# Sheet1.net
KiCad netlist of a schematic drawn in Altium Designer
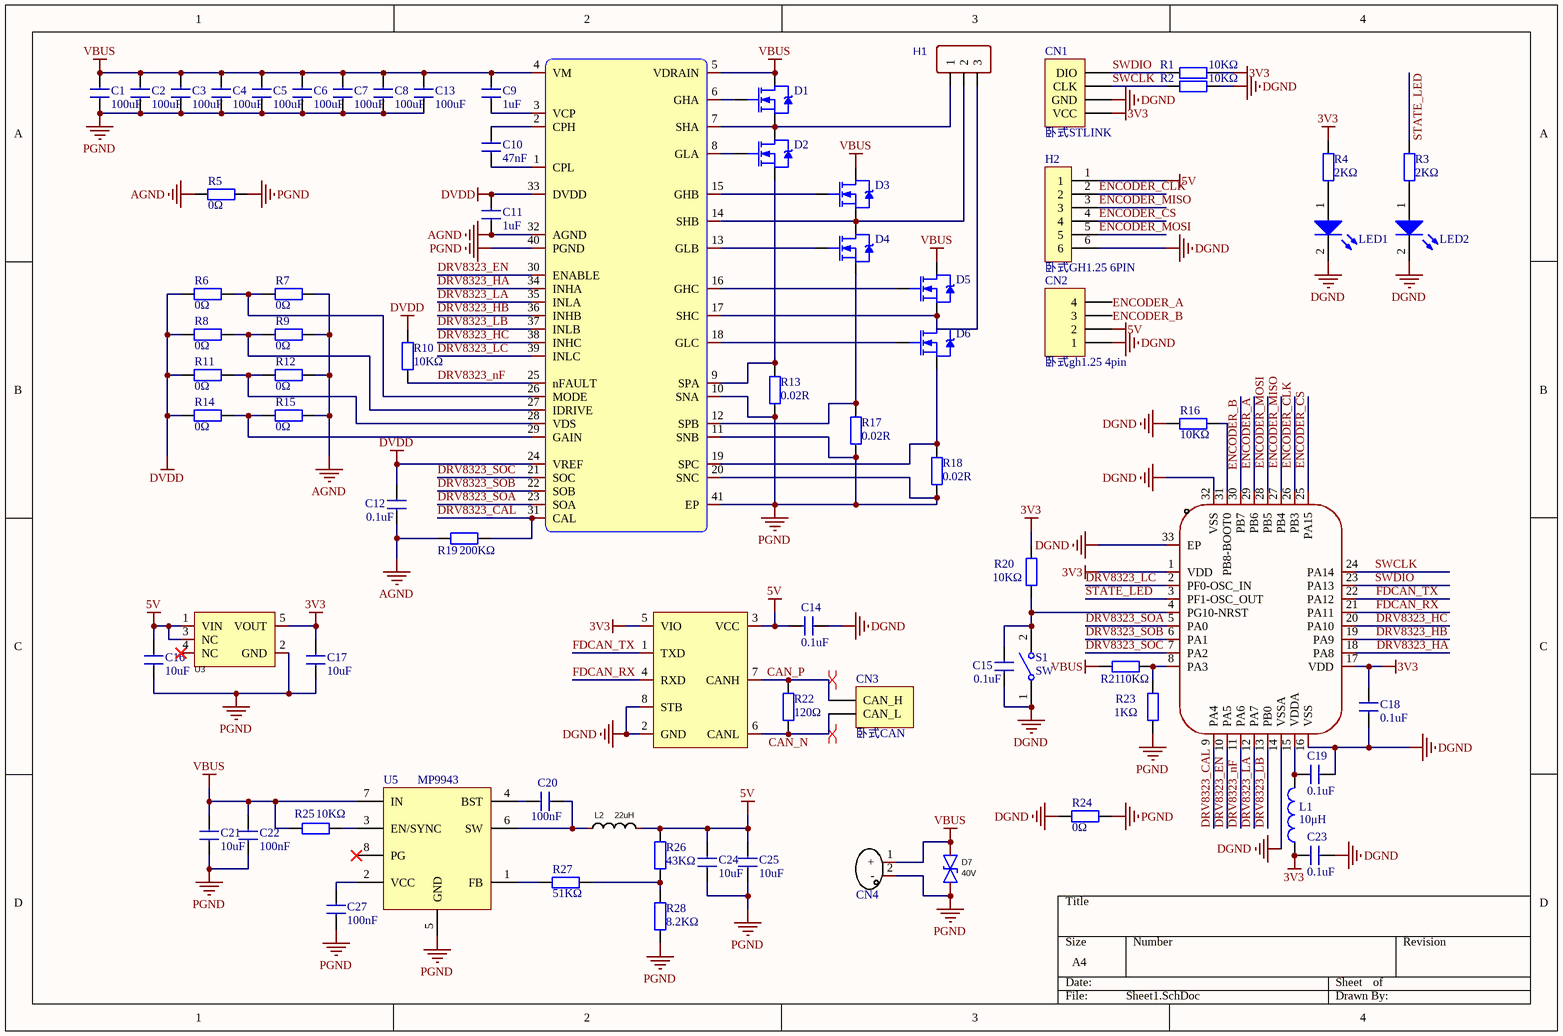
[diagram p0: Sheet1.SchDoc]

(export (version "E")
  (design (tool "Eeschema 10.0.6"))
  (components
    (comp (ref "C1")
      (value "100uF")
      (footprint "1210")
      (description "1210贴片电容")
      (libsource (lib "Integrated_Library1") (part "1210贴片电容"))
    )
    (comp (ref "C2")
      (value "100uF")
      (footprint "1210")
      (description "1210贴片电容")
      (libsource (lib "Integrated_Library1") (part "1210贴片电容"))
    )
    (comp (ref "C3")
      (value "100uF")
      (footprint "1210")
      (description "1210贴片电容")
      (libsource (lib "Integrated_Library1") (part "1210贴片电容"))
    )
    (comp (ref "C4")
      (value "100uF")
      (footprint "1210")
      (description "1210贴片电容")
      (libsource (lib "Integrated_Library1") (part "1210贴片电容"))
    )
    (comp (ref "C5")
      (value "100uF")
      (footprint "1210")
      (description "1210贴片电容")
      (libsource (lib "Integrated_Library1") (part "1210贴片电容"))
    )
    (comp (ref "C6")
      (value "100uF")
      (footprint "1210")
      (description "1210贴片电容")
      (libsource (lib "Integrated_Library1") (part "1210贴片电容"))
    )
    (comp (ref "C7")
      (value "100uF")
      (footprint "1210")
      (description "1210贴片电容")
      (libsource (lib "Integrated_Library1") (part "1210贴片电容"))
    )
    (comp (ref "C8")
      (value "100uF")
      (footprint "1210")
      (description "1210贴片电容")
      (libsource (lib "Integrated_Library1") (part "1210贴片电容"))
    )
    (comp (ref "C9")
      (value "1uF")
      (footprint "c0402")
      (description "贴片电容0402")
      (libsource (lib "Integrated_Library1") (part "0402贴片电容"))
    )
    (comp (ref "C10")
      (value "47nF")
      (footprint "c0402")
      (description "贴片电容0402")
      (libsource (lib "Integrated_Library1") (part "0402贴片电容"))
    )
    (comp (ref "C11")
      (value "1uF")
      (footprint "c0402")
      (description "贴片电容0402")
      (libsource (lib "Integrated_Library1") (part "0402贴片电容"))
    )
    (comp (ref "C12")
      (value "0.1uF")
      (footprint "c0402")
      (description "贴片电容0402")
      (libsource (lib "Integrated_Library1") (part "0402贴片电容"))
    )
    (comp (ref "C13")
      (value "100uF")
      (footprint "1210")
      (description "1210贴片电容")
      (libsource (lib "Integrated_Library1") (part "1210贴片电容"))
    )
    (comp (ref "C14")
      (value "0.1uF")
      (footprint "c0402")
      (description "贴片电容0402")
      (libsource (lib "Integrated_Library1") (part "0402贴片电容"))
    )
    (comp (ref "C15")
      (value "0.1uF")
      (footprint "c0402")
      (description "贴片电容0402")
      (libsource (lib "Integrated_Library1") (part "0402贴片电容"))
    )
    (comp (ref "C16")
      (value "10uF")
      (footprint "c0402")
      (description "贴片电容0402")
      (libsource (lib "Integrated_Library1") (part "0402贴片电容"))
    )
    (comp (ref "C17")
      (value "10uF")
      (footprint "c0402")
      (description "贴片电容0402")
      (libsource (lib "Integrated_Library1") (part "0402贴片电容"))
    )
    (comp (ref "C18")
      (value "0.1uF")
      (footprint "c0402")
      (description "贴片电容0402")
      (libsource (lib "Integrated_Library1") (part "0402贴片电容"))
    )
    (comp (ref "C19")
      (value "0.1uF")
      (footprint "c0402")
      (description "贴片电容0402")
      (libsource (lib "Integrated_Library1") (part "0402贴片电容"))
    )
    (comp (ref "C20")
      (value "100nF")
      (footprint "c0402")
      (description "贴片电容0402")
      (libsource (lib "Integrated_Library1") (part "0402贴片电容"))
    )
    (comp (ref "C21")
      (value "10uF")
      (footprint "1210")
      (description "1210贴片电容")
      (libsource (lib "Integrated_Library1") (part "1210贴片电容"))
    )
    (comp (ref "C22")
      (value "100nF")
      (footprint "c0402")
      (description "贴片电容0402")
      (libsource (lib "Integrated_Library1") (part "0402贴片电容"))
    )
    (comp (ref "C23")
      (value "0.1uF")
      (footprint "c0402")
      (description "贴片电容0402")
      (libsource (lib "Integrated_Library1") (part "0402贴片电容"))
    )
    (comp (ref "C24")
      (value "10uF")
      (footprint "1210")
      (description "1210贴片电容")
      (libsource (lib "Integrated_Library1") (part "1210贴片电容"))
    )
    (comp (ref "C25")
      (value "10uF")
      (footprint "1210")
      (description "1210贴片电容")
      (libsource (lib "Integrated_Library1") (part "1210贴片电容"))
    )
    (comp (ref "C27")
      (value "100nF")
      (footprint "c0402")
      (description "贴片电容0402")
      (libsource (lib "Integrated_Library1") (part "0402贴片电容"))
    )
    (comp (ref "CN1")
      (value "卧式STLINK")
      (footprint "CONN-SMD_4P-P1.25_GH1.25-4P")
      (libsource (lib "Integrated_Library1") (part "卧式STLINK"))
    )
    (comp (ref "CN2")
      (value "卧式gh1.25 4pin")
      (footprint "CONN-SMD_4P-P1.25_GH1.25-4P")
      (libsource (lib "Integrated_Library1") (part "卧式gh1.25 4pin"))
    )
    (comp (ref "CN3")
      (value "卧式CAN")
      (footprint "A1257WR-S-2P")
      (fields (field (name "PUBLISHER") "Altium Limited"))
      (libsource (lib "Integrated_Library1") (part "卧式CAN"))
    )
    (comp (ref "CN4")
      (value "卧贴立式XT30母头")
      (footprint "CONN-TH_XT30U-M _Sleep")
      (libsource (lib "Integrated_Library1") (part "卧贴立式XT30母头"))
    )
    (comp (ref "D1")
      (value "CSD18540")
      (footprint "pg-tdson-8")
      (description "N沟道MOS管")
      (fields (field (name "PUBLISHER") "Altium Limited"))
      (libsource (lib "Integrated_Library1") (part "CSD18540"))
    )
    (comp (ref "D2")
      (value "CSD18540")
      (footprint "pg-tdson-8")
      (description "N沟道MOS管")
      (fields (field (name "PUBLISHER") "Altium Limited"))
      (libsource (lib "Integrated_Library1") (part "CSD18540"))
    )
    (comp (ref "D3")
      (value "CSD18540")
      (footprint "pg-tdson-8")
      (description "N沟道MOS管")
      (fields (field (name "PUBLISHER") "Altium Limited"))
      (libsource (lib "Integrated_Library1") (part "CSD18540"))
    )
    (comp (ref "D4")
      (value "CSD18540")
      (footprint "pg-tdson-8")
      (description "N沟道MOS管")
      (fields (field (name "PUBLISHER") "Altium Limited"))
      (libsource (lib "Integrated_Library1") (part "CSD18540"))
    )
    (comp (ref "D5")
      (value "CSD18540")
      (footprint "pg-tdson-8")
      (description "N沟道MOS管")
      (fields (field (name "PUBLISHER") "Altium Limited"))
      (libsource (lib "Integrated_Library1") (part "CSD18540"))
    )
    (comp (ref "D6")
      (value "CSD18540")
      (footprint "pg-tdson-8")
      (description "N沟道MOS管")
      (fields (field (name "PUBLISHER") "Altium Limited"))
      (libsource (lib "Integrated_Library1") (part "CSD18540"))
    )
    (comp (ref "D7")
      (value "40V")
      (footprint "SMB_L4.6-W3.6-LS5.3-BI")
      (description "28V 双向TVS")
      (fields (field (name "MANUFACTURER") "Littelfuse(美国力特)") (field (name "MANUFACTURER PART") "P6SMB30CA"))
      (libsource (lib "Integrated_Library1") (part "P6SMB30CA"))
    )
    (comp (ref "H1")
      (value "MR30-M")
      (footprint "MR30")
      (fields (field (name "BOM_SUPPLIER PART") "C99873") (field (name "CONTRIBUTOR") "LCEDA_Lib"))
      (libsource (lib "Integrated_Library1") (part "MR30-M"))
    )
    (comp (ref "H2")
      (value "卧式GH1.25 6PIN")
      (footprint "CONN-SMD_6P-P1.25_XYECONN_XY-GH1.25-6A61")
      (libsource (lib "Integrated_Library1") (part "卧式GH1.25 6PIN"))
    )
    (comp (ref "L1")
      (value "10μH")
      (footprint "L0805")
      (description "0805贴片电感")
      (libsource (lib "Integrated_Library1") (part "0805贴片电感"))
    )
    (comp (ref "L2")
      (value "22uH")
      (footprint "IND-SMD_L5.4-W5.2")
      (description "一体成型屏蔽电感，0530封装，额定电流3A")
      (fields (field (name "MANUFACTURER") "XR(祥如)") (field (name "MANUFACTURER PART") "XR0530-100M"))
      (libsource (lib "Integrated_Library1") (part "0530屏蔽电感"))
    )
    (comp (ref "LED1")
      (value "LED")
      (footprint "led0805")
      (description "0805贴片LED")
      (libsource (lib "Integrated_Library1") (part "0805贴片LED"))
    )
    (comp (ref "LED2")
      (value "LED")
      (footprint "led0805")
      (description "0805贴片LED")
      (libsource (lib "Integrated_Library1") (part "0805贴片LED"))
    )
    (comp (ref "R1")
      (value "10KΩ")
      (footprint "R0402")
      (description "0402贴片电阻")
      (libsource (lib "Integrated_Library1") (part "0402贴片电阻"))
    )
    (comp (ref "R2")
      (value "10KΩ")
      (footprint "R0402")
      (description "0402贴片电阻")
      (libsource (lib "Integrated_Library1") (part "0402贴片电阻"))
    )
    (comp (ref "R3")
      (value "2KΩ")
      (footprint "R0402")
      (description "0402贴片电阻")
      (libsource (lib "") (part "0402贴片电阻_2"))
    )
    (comp (ref "R4")
      (value "2KΩ")
      (footprint "R0402")
      (description "0402贴片电阻")
      (libsource (lib "") (part "0402贴片电阻_2"))
    )
    (comp (ref "R5")
      (value "0Ω")
      (footprint "R0402")
      (description "0402贴片电阻")
      (libsource (lib "Integrated_Library1") (part "0402贴片电阻"))
    )
    (comp (ref "R6")
      (value "0Ω")
      (footprint "R0402")
      (description "0402贴片电阻")
      (libsource (lib "Integrated_Library1") (part "0402贴片电阻"))
    )
    (comp (ref "R7")
      (value "0Ω")
      (footprint "R0402")
      (description "0402贴片电阻")
      (libsource (lib "Integrated_Library1") (part "0402贴片电阻"))
    )
    (comp (ref "R8")
      (value "0Ω")
      (footprint "R0402")
      (description "0402贴片电阻")
      (libsource (lib "Integrated_Library1") (part "0402贴片电阻"))
    )
    (comp (ref "R9")
      (value "0Ω")
      (footprint "R0402")
      (description "0402贴片电阻")
      (libsource (lib "Integrated_Library1") (part "0402贴片电阻"))
    )
    (comp (ref "R10")
      (value "10KΩ")
      (footprint "R0402")
      (description "0402贴片电阻")
      (libsource (lib "") (part "0402贴片电阻_2"))
    )
    (comp (ref "R11")
      (value "0Ω")
      (footprint "R0402")
      (description "0402贴片电阻")
      (libsource (lib "Integrated_Library1") (part "0402贴片电阻"))
    )
    (comp (ref "R12")
      (value "0Ω")
      (footprint "R0402")
      (description "0402贴片电阻")
      (libsource (lib "Integrated_Library1") (part "0402贴片电阻"))
    )
    (comp (ref "R13")
      (value "0.02R")
      (footprint "R 2512_M")
      (description "2512检流电阻")
      (libsource (lib "Integrated_Library1") (part "2512检流电阻"))
    )
    (comp (ref "R14")
      (value "0Ω")
      (footprint "R0402")
      (description "0402贴片电阻")
      (libsource (lib "Integrated_Library1") (part "0402贴片电阻"))
    )
    (comp (ref "R15")
      (value "0Ω")
      (footprint "R0402")
      (description "0402贴片电阻")
      (libsource (lib "Integrated_Library1") (part "0402贴片电阻"))
    )
    (comp (ref "R16")
      (value "10KΩ")
      (footprint "R0402")
      (description "0402贴片电阻")
      (libsource (lib "Integrated_Library1") (part "0402贴片电阻"))
    )
    (comp (ref "R17")
      (value "0.02R")
      (footprint "R 2512_M")
      (description "2512检流电阻")
      (libsource (lib "Integrated_Library1") (part "2512检流电阻"))
    )
    (comp (ref "R18")
      (value "0.02R")
      (footprint "R 2512_M")
      (description "2512检流电阻")
      (libsource (lib "Integrated_Library1") (part "2512检流电阻"))
    )
    (comp (ref "R19")
      (value "200KΩ")
      (footprint "R0402")
      (description "0402贴片电阻")
      (libsource (lib "") (part "0402贴片电阻_5"))
    )
    (comp (ref "R20")
      (value "10KΩ")
      (footprint "R0402")
      (description "0402贴片电阻")
      (libsource (lib "") (part "0402贴片电阻_2"))
    )
    (comp (ref "R21")
      (value "10KΩ")
      (footprint "R0402")
      (description "0402贴片电阻")
      (libsource (lib "") (part "0402贴片电阻_5"))
    )
    (comp (ref "R22")
      (value "120Ω")
      (footprint "R0402")
      (description "0402贴片电阻")
      (libsource (lib "") (part "0402贴片电阻_1"))
    )
    (comp (ref "R23")
      (value "1KΩ")
      (footprint "R0402")
      (description "0402贴片电阻")
      (libsource (lib "") (part "0402贴片电阻_2"))
    )
    (comp (ref "R24")
      (value "0Ω")
      (footprint "R0402")
      (description "0402贴片电阻")
      (libsource (lib "Integrated_Library1") (part "0402贴片电阻"))
    )
    (comp (ref "R25")
      (value "10KΩ")
      (footprint "R0402")
      (description "0402贴片电阻")
      (libsource (lib "") (part "0402贴片电阻_3"))
    )
    (comp (ref "R26")
      (value "43KΩ")
      (footprint "R0402")
      (description "0402贴片电阻")
      (libsource (lib "") (part "0402贴片电阻_4"))
    )
    (comp (ref "R27")
      (value "51KΩ")
      (footprint "R0402")
      (description "0402贴片电阻")
      (libsource (lib "") (part "0402贴片电阻_3"))
    )
    (comp (ref "R28")
      (value "8.2KΩ")
      (footprint "R0402")
      (description "0402贴片电阻")
      (libsource (lib "") (part "0402贴片电阻_4"))
    )
    (comp (ref "S1")
      (value "SW")
      (footprint "KEY_SMD")
      (description "开关")
      (libsource (lib "Integrated_Library1") (part "SW"))
    )
    (comp (ref "U1")
      (value "STM32G431KBU3")
      (footprint "UFQFPN-32_L5.0-W5.0-P0.50-BL-EP3.5")
      (fields (field (name "MANUFACTURER") "ST(意法半导体)"))
      (libsource (lib "Integrated_Library1") (part "STM32G431KBU3"))
    )
    (comp (ref "U2")
      (value "DRV8323HRTAR")
      (footprint "QFN-40_L6.0-W6.0-P0.50-BL-EP4.5")
      (fields (field (name "MANUFACTURER") "TI(德州仪器)"))
      (libsource (lib "Integrated_Library1") (part "DRV8323HRTAR"))
    )
    (comp (ref "U3")
      (value "XC6201P332MR-HXY")
      (footprint "SOT-23-5_L3.0-W1.7-P0.95-LS2.8-BR")
      (description "3.3V LDO")
      (fields (field (name "MANUFACTURER") "HXY MOSFET(华轩阳电子)"))
      (libsource (lib "Integrated_Library1") (part "XC6201P332MR-HXY"))
    )
    (comp (ref "U4")
      (value "TCAN1042VDRQ1")
      (footprint "SOIC-8_L4.9-W3.9-P1.27-LS6.0-BL")
      (fields (field (name "MANUFACTURER") "TI(德州仪器)"))
      (libsource (lib "Integrated_Library1") (part "TCAN1042VDRQ1"))
    )
    (comp (ref "U5")
      (value "MP9943")
      (footprint "QFN-8 3x3")
      (libsource (lib "Integrated_Library1") (part "MP9943"))
    )
  )
  (nets
    (net (code "1") (name "/CAN_N") (class "Default")
      (node (ref "CN3") (pin "2") (pinfunction "CAN_L_2") (pintype "passive"))
      (node (ref "R22") (pin "1") (pinfunction "1_1") (pintype "passive"))
      (node (ref "U4") (pin "6") (pinfunction "CANL_6") (pintype "passive"))
    )
    (net (code "2") (name "/CAN_P") (class "Default")
      (node (ref "CN3") (pin "1") (pinfunction "CAN_H_1") (pintype "passive"))
      (node (ref "R22") (pin "2") (pinfunction "2_2") (pintype "passive"))
      (node (ref "U4") (pin "7") (pinfunction "CANH_7") (pintype "passive"))
    )
    (net (code "3") (name "/DRV8323_CAL") (class "Default")
      (node (ref "R19") (pin "1") (pinfunction "1_1") (pintype "passive"))
      (node (ref "U1") (pin "9") (pinfunction "PA4_9") (pintype "passive"))
      (node (ref "U2") (pin "31") (pinfunction "CAL_31") (pintype "passive"))
    )
    (net (code "4") (name "/DRV8323_EN") (class "Default")
      (node (ref "U1") (pin "10") (pinfunction "PA5_10") (pintype "passive"))
      (node (ref "U2") (pin "30") (pinfunction "ENABLE_30") (pintype "passive"))
    )
    (net (code "5") (name "/DRV8323_HA") (class "Default")
      (node (ref "U1") (pin "18") (pinfunction "PA8_18") (pintype "passive"))
      (node (ref "U2") (pin "34") (pinfunction "INHA_34") (pintype "passive"))
    )
    (net (code "6") (name "/DRV8323_HB") (class "Default")
      (node (ref "U1") (pin "19") (pinfunction "PA9_19") (pintype "passive"))
      (node (ref "U2") (pin "36") (pinfunction "INHB_36") (pintype "passive"))
    )
    (net (code "7") (name "/DRV8323_HC") (class "Default")
      (node (ref "U1") (pin "20") (pinfunction "PA10_20") (pintype "passive"))
      (node (ref "U2") (pin "38") (pinfunction "INHC_38") (pintype "passive"))
    )
    (net (code "8") (name "/DRV8323_LA") (class "Default")
      (node (ref "U1") (pin "12") (pinfunction "PA7_12") (pintype "passive"))
      (node (ref "U2") (pin "35") (pinfunction "INLA_35") (pintype "passive"))
    )
    (net (code "9") (name "/DRV8323_LB") (class "Default")
      (node (ref "U1") (pin "13") (pinfunction "PB0_13") (pintype "passive"))
      (node (ref "U2") (pin "37") (pinfunction "INLB_37") (pintype "passive"))
    )
    (net (code "10") (name "/DRV8323_LC") (class "Default")
      (node (ref "U1") (pin "2") (pinfunction "PF0-OSC_IN_2") (pintype "passive"))
      (node (ref "U2") (pin "39") (pinfunction "INLC_39") (pintype "passive"))
    )
    (net (code "11") (name "/DRV8323_SOA") (class "Default")
      (node (ref "U1") (pin "5") (pinfunction "PA0_5") (pintype "passive"))
      (node (ref "U2") (pin "23") (pinfunction "SOA_23") (pintype "passive"))
    )
    (net (code "12") (name "/DRV8323_SOB") (class "Default")
      (node (ref "U1") (pin "6") (pinfunction "PA1_6") (pintype "passive"))
      (node (ref "U2") (pin "22") (pinfunction "SOB_22") (pintype "passive"))
    )
    (net (code "13") (name "/DRV8323_SOC") (class "Default")
      (node (ref "U1") (pin "7") (pinfunction "PA2_7") (pintype "passive"))
      (node (ref "U2") (pin "21") (pinfunction "SOC_21") (pintype "passive"))
    )
    (net (code "14") (name "/DRV8323_nF") (class "Default")
      (node (ref "R10") (pin "2") (pinfunction "2_2") (pintype "passive"))
      (node (ref "U1") (pin "11") (pinfunction "PA6_11") (pintype "passive"))
      (node (ref "U2") (pin "25") (pinfunction "nFAULT_25") (pintype "passive"))
    )
    (net (code "15") (name "/ENCODER_A") (class "Default")
      (node (ref "CN2") (pin "4") (pinfunction "4_4") (pintype "passive"))
      (node (ref "U1") (pin "29") (pinfunction "PB6_29") (pintype "passive"))
    )
    (net (code "16") (name "/ENCODER_B") (class "Default")
      (node (ref "CN2") (pin "3") (pinfunction "3_3") (pintype "passive"))
      (node (ref "U1") (pin "30") (pinfunction "PB7_30") (pintype "passive"))
    )
    (net (code "17") (name "/ENCODER_CLK") (class "Default")
      (node (ref "H2") (pin "2") (pinfunction "2_2") (pintype "passive"))
      (node (ref "U1") (pin "26") (pinfunction "PB3_26") (pintype "passive"))
    )
    (net (code "18") (name "/ENCODER_CS") (class "Default")
      (node (ref "H2") (pin "4") (pinfunction "4_4") (pintype "passive"))
      (node (ref "U1") (pin "25") (pinfunction "PA15_25") (pintype "passive"))
    )
    (net (code "19") (name "/ENCODER_MISO") (class "Default")
      (node (ref "H2") (pin "3") (pinfunction "3_3") (pintype "passive"))
      (node (ref "U1") (pin "27") (pinfunction "PB4_27") (pintype "passive"))
    )
    (net (code "20") (name "/ENCODER_MOSI") (class "Default")
      (node (ref "H2") (pin "5") (pinfunction "5_5") (pintype "passive"))
      (node (ref "U1") (pin "28") (pinfunction "PB5_28") (pintype "passive"))
    )
    (net (code "21") (name "/FDCAN_RX") (class "Default")
      (node (ref "U1") (pin "21") (pinfunction "PA11_21") (pintype "passive"))
      (node (ref "U4") (pin "4") (pinfunction "RXD_4") (pintype "passive"))
    )
    (net (code "22") (name "/FDCAN_TX") (class "Default")
      (node (ref "U1") (pin "22") (pinfunction "PA12_22") (pintype "passive"))
      (node (ref "U4") (pin "1") (pinfunction "TXD_1") (pintype "passive"))
    )
    (net (code "23") (name "/STATE_LED") (class "Default")
      (node (ref "R3") (pin "1") (pinfunction "1_1") (pintype "passive"))
      (node (ref "U1") (pin "3") (pinfunction "PF1-OSC_OUT_3") (pintype "passive"))
    )
    (net (code "24") (name "/SWCLK") (class "Default")
      (node (ref "CN1") (pin "3") (pinfunction "CLK_3") (pintype "passive"))
      (node (ref "R2") (pin "1") (pinfunction "1_1") (pintype "passive"))
      (node (ref "U1") (pin "24") (pinfunction "PA14_24") (pintype "passive"))
    )
    (net (code "25") (name "/SWDIO") (class "Default")
      (node (ref "CN1") (pin "4") (pinfunction "DIO_4") (pintype "passive"))
      (node (ref "R1") (pin "1") (pinfunction "1_1") (pintype "passive"))
      (node (ref "U1") (pin "23") (pinfunction "PA13_23") (pintype "passive"))
    )
    (net (code "26") (name "3V3") (class "Default")
      (node (ref "C17") (pin "2") (pinfunction "2_2") (pintype "passive"))
      (node (ref "C18") (pin "1") (pinfunction "1_1") (pintype "passive"))
      (node (ref "C23") (pin "2") (pinfunction "2_2") (pintype "passive"))
      (node (ref "CN1") (pin "1") (pinfunction "VCC_1") (pintype "passive"))
      (node (ref "L1") (pin "1") (pinfunction "1_1") (pintype "passive"))
      (node (ref "R1") (pin "2") (pinfunction "2_2") (pintype "passive"))
      (node (ref "R20") (pin "1") (pinfunction "1_1") (pintype "passive"))
      (node (ref "R4") (pin "1") (pinfunction "1_1") (pintype "passive"))
      (node (ref "U1") (pin "1") (pinfunction "VDD_1") (pintype "passive"))
      (node (ref "U1") (pin "17") (pinfunction "VDD_17") (pintype "passive"))
      (node (ref "U3") (pin "5") (pinfunction "VOUT_5") (pintype "passive"))
      (node (ref "U4") (pin "5") (pinfunction "VIO_5") (pintype "passive"))
    )
    (net (code "27") (name "5V") (class "Default")
      (node (ref "C14") (pin "2") (pinfunction "2_2") (pintype "passive"))
      (node (ref "C16") (pin "2") (pinfunction "2_2") (pintype "passive"))
      (node (ref "C24") (pin "2") (pinfunction "2_2") (pintype "passive"))
      (node (ref "C25") (pin "2") (pinfunction "2_2") (pintype "passive"))
      (node (ref "CN2") (pin "2") (pinfunction "2_2") (pintype "passive"))
      (node (ref "H2") (pin "1") (pinfunction "1_1") (pintype "passive"))
      (node (ref "L2") (pin "2") (pinfunction "2_2") (pintype "passive"))
      (node (ref "R26") (pin "2") (pinfunction "2_2") (pintype "passive"))
      (node (ref "U3") (pin "1") (pinfunction "VIN_1") (pintype "passive"))
      (node (ref "U3") (pin "3") (pinfunction "NC_3") (pintype "passive"))
      (node (ref "U4") (pin "3") (pinfunction "VCC_3") (pintype "passive"))
    )
    (net (code "28") (name "AGND") (class "Default")
      (node (ref "C11") (pin "1") (pinfunction "1_1") (pintype "passive"))
      (node (ref "C12") (pin "1") (pinfunction "1_1") (pintype "passive"))
      (node (ref "R12") (pin "2") (pinfunction "2_2") (pintype "passive"))
      (node (ref "R15") (pin "2") (pinfunction "2_2") (pintype "passive"))
      (node (ref "R19") (pin "2") (pinfunction "2_2") (pintype "passive"))
      (node (ref "R5") (pin "1") (pinfunction "1_1") (pintype "passive"))
      (node (ref "R7") (pin "2") (pinfunction "2_2") (pintype "passive"))
      (node (ref "R9") (pin "2") (pinfunction "2_2") (pintype "passive"))
      (node (ref "U2") (pin "32") (pinfunction "AGND_32") (pintype "passive"))
    )
    (net (code "29") (name "DGND") (class "Default")
      (node (ref "C14") (pin "1") (pinfunction "1_1") (pintype "passive"))
      (node (ref "C15") (pin "1") (pinfunction "1_1") (pintype "passive"))
      (node (ref "C18") (pin "2") (pinfunction "2_2") (pintype "passive"))
      (node (ref "C19") (pin "1") (pinfunction "1_1") (pintype "passive"))
      (node (ref "C23") (pin "1") (pinfunction "1_1") (pintype "passive"))
      (node (ref "CN1") (pin "2") (pinfunction "GND_2") (pintype "passive"))
      (node (ref "CN2") (pin "1") (pinfunction "1_1") (pintype "passive"))
      (node (ref "H2") (pin "6") (pinfunction "6_6") (pintype "passive"))
      (node (ref "LED1") (pin "2") (pinfunction "K_2") (pintype "passive"))
      (node (ref "LED2") (pin "2") (pinfunction "K_2") (pintype "passive"))
      (node (ref "R16") (pin "1") (pinfunction "1_1") (pintype "passive"))
      (node (ref "R2") (pin "2") (pinfunction "2_2") (pintype "passive"))
      (node (ref "R24") (pin "1") (pinfunction "1_1") (pintype "passive"))
      (node (ref "S1") (pin "1") (pinfunction "COMMON_1") (pintype "passive"))
      (node (ref "U1") (pin "14") (pinfunction "VSSA_14") (pintype "passive"))
      (node (ref "U1") (pin "16") (pinfunction "VSS_16") (pintype "passive"))
      (node (ref "U1") (pin "32") (pinfunction "VSS_32") (pintype "passive"))
      (node (ref "U1") (pin "33") (pinfunction "EP_33") (pintype "passive"))
      (node (ref "U4") (pin "2") (pinfunction "GND_2") (pintype "passive"))
      (node (ref "U4") (pin "8") (pinfunction "STB_8") (pintype "passive"))
    )
    (net (code "30") (name "DVDD") (class "Default")
      (node (ref "C11") (pin "2") (pinfunction "2_2") (pintype "passive"))
      (node (ref "C12") (pin "2") (pinfunction "2_2") (pintype "passive"))
      (node (ref "R10") (pin "1") (pinfunction "1_1") (pintype "passive"))
      (node (ref "R11") (pin "1") (pinfunction "1_1") (pintype "passive"))
      (node (ref "R14") (pin "1") (pinfunction "1_1") (pintype "passive"))
      (node (ref "R6") (pin "1") (pinfunction "1_1") (pintype "passive"))
      (node (ref "R8") (pin "1") (pinfunction "1_1") (pintype "passive"))
      (node (ref "U2") (pin "24") (pinfunction "VREF_24") (pintype "passive"))
      (node (ref "U2") (pin "33") (pinfunction "DVDD_33") (pintype "passive"))
    )
    (net (code "31") (name "Net-(D1-G)") (class "Default")
      (node (ref "D1") (pin "1") (pinfunction "G_1") (pintype "passive"))
      (node (ref "U2") (pin "6") (pinfunction "GHA_6") (pintype "passive"))
    )
    (net (code "32") (name "Net-(D1-S)") (class "Default")
      (node (ref "D1") (pin "3") (pinfunction "S_3") (pintype "passive"))
      (node (ref "D2") (pin "2") (pinfunction "D_2") (pintype "passive"))
      (node (ref "H1") (pin "1") (pinfunction "1_1") (pintype "passive"))
      (node (ref "U2") (pin "7") (pinfunction "SHA_7") (pintype "passive"))
    )
    (net (code "33") (name "Net-(D2-G)") (class "Default")
      (node (ref "D2") (pin "1") (pinfunction "G_1") (pintype "passive"))
      (node (ref "U2") (pin "8") (pinfunction "GLA_8") (pintype "passive"))
    )
    (net (code "34") (name "Net-(D2-S)") (class "Default")
      (node (ref "D2") (pin "3") (pinfunction "S_3") (pintype "passive"))
      (node (ref "R13") (pin "2") (pinfunction "2_2") (pintype "passive"))
      (node (ref "U2") (pin "9") (pinfunction "SPA_9") (pintype "passive"))
    )
    (net (code "35") (name "Net-(D3-G)") (class "Default")
      (node (ref "D3") (pin "1") (pinfunction "G_1") (pintype "passive"))
      (node (ref "U2") (pin "15") (pinfunction "GHB_15") (pintype "passive"))
    )
    (net (code "36") (name "Net-(D3-S)") (class "Default")
      (node (ref "D3") (pin "3") (pinfunction "S_3") (pintype "passive"))
      (node (ref "D4") (pin "2") (pinfunction "D_2") (pintype "passive"))
      (node (ref "H1") (pin "2") (pinfunction "2_2") (pintype "passive"))
      (node (ref "U2") (pin "14") (pinfunction "SHB_14") (pintype "passive"))
    )
    (net (code "37") (name "Net-(D4-G)") (class "Default")
      (node (ref "D4") (pin "1") (pinfunction "G_1") (pintype "passive"))
      (node (ref "U2") (pin "13") (pinfunction "GLB_13") (pintype "passive"))
    )
    (net (code "38") (name "Net-(D4-S)") (class "Default")
      (node (ref "D4") (pin "3") (pinfunction "S_3") (pintype "passive"))
      (node (ref "R17") (pin "2") (pinfunction "2_2") (pintype "passive"))
      (node (ref "U2") (pin "12") (pinfunction "SPB_12") (pintype "passive"))
    )
    (net (code "39") (name "Net-(D5-G)") (class "Default")
      (node (ref "D5") (pin "1") (pinfunction "G_1") (pintype "passive"))
      (node (ref "U2") (pin "16") (pinfunction "GHC_16") (pintype "passive"))
    )
    (net (code "40") (name "Net-(D5-S)") (class "Default")
      (node (ref "D5") (pin "3") (pinfunction "S_3") (pintype "passive"))
      (node (ref "D6") (pin "2") (pinfunction "D_2") (pintype "passive"))
      (node (ref "H1") (pin "3") (pinfunction "3_3") (pintype "passive"))
      (node (ref "U2") (pin "17") (pinfunction "SHC_17") (pintype "passive"))
    )
    (net (code "41") (name "Net-(D6-G)") (class "Default")
      (node (ref "D6") (pin "1") (pinfunction "G_1") (pintype "passive"))
      (node (ref "U2") (pin "18") (pinfunction "GLC_18") (pintype "passive"))
    )
    (net (code "42") (name "Net-(D6-S)") (class "Default")
      (node (ref "D6") (pin "3") (pinfunction "S_3") (pintype "passive"))
      (node (ref "R18") (pin "2") (pinfunction "2_2") (pintype "passive"))
      (node (ref "U2") (pin "19") (pinfunction "SPC_19") (pintype "passive"))
    )
    (net (code "43") (name "Net-(LED1-A)") (class "Default")
      (node (ref "LED1") (pin "1") (pinfunction "A_1") (pintype "passive"))
      (node (ref "R4") (pin "2") (pinfunction "2_2") (pintype "passive"))
    )
    (net (code "44") (name "Net-(LED2-A)") (class "Default")
      (node (ref "LED2") (pin "1") (pinfunction "A_1") (pintype "passive"))
      (node (ref "R3") (pin "2") (pinfunction "2_2") (pintype "passive"))
    )
    (net (code "45") (name "Net-(R26-Pad1)") (class "Default")
      (node (ref "R26") (pin "1") (pinfunction "1_1") (pintype "passive"))
      (node (ref "R27") (pin "2") (pinfunction "2_2") (pintype "passive"))
      (node (ref "R28") (pin "2") (pinfunction "2_2") (pintype "passive"))
    )
    (net (code "46") (name "Net-(S1-NO)") (class "Default")
      (node (ref "C15") (pin "2") (pinfunction "2_2") (pintype "passive"))
      (node (ref "R20") (pin "2") (pinfunction "2_2") (pintype "passive"))
      (node (ref "S1") (pin "2") (pinfunction "NO_2") (pintype "passive"))
      (node (ref "U1") (pin "4") (pinfunction "PG10-NRST_4") (pintype "passive"))
    )
    (net (code "47") (name "Net-(U1-PA3)") (class "Default")
      (node (ref "R21") (pin "1") (pinfunction "1_1") (pintype "passive"))
      (node (ref "R23") (pin "1") (pinfunction "1_1") (pintype "passive"))
      (node (ref "U1") (pin "8") (pinfunction "PA3_8") (pintype "passive"))
    )
    (net (code "48") (name "Net-(U1-PB8-BOOT0)") (class "Default")
      (node (ref "R16") (pin "2") (pinfunction "2_2") (pintype "passive"))
      (node (ref "U1") (pin "31") (pinfunction "PB8-BOOT0_31") (pintype "passive"))
    )
    (net (code "49") (name "Net-(U1-VDDA)") (class "Default")
      (node (ref "C19") (pin "2") (pinfunction "2_2") (pintype "passive"))
      (node (ref "L1") (pin "2") (pinfunction "2_2") (pintype "passive"))
      (node (ref "U1") (pin "15") (pinfunction "VDDA_15") (pintype "passive"))
    )
    (net (code "50") (name "Net-(U2-CPH)") (class "Default")
      (node (ref "C10") (pin "2") (pinfunction "2_2") (pintype "passive"))
      (node (ref "U2") (pin "2") (pinfunction "CPH_2") (pintype "passive"))
    )
    (net (code "51") (name "Net-(U2-CPL)") (class "Default")
      (node (ref "C10") (pin "1") (pinfunction "1_1") (pintype "passive"))
      (node (ref "U2") (pin "1") (pinfunction "CPL_1") (pintype "passive"))
    )
    (net (code "52") (name "Net-(U2-GAIN)") (class "Default")
      (node (ref "R14") (pin "2") (pinfunction "2_2") (pintype "passive"))
      (node (ref "R15") (pin "1") (pinfunction "1_1") (pintype "passive"))
      (node (ref "U2") (pin "29") (pinfunction "GAIN_29") (pintype "passive"))
    )
    (net (code "53") (name "Net-(U2-IDRIVE)") (class "Default")
      (node (ref "R8") (pin "2") (pinfunction "2_2") (pintype "passive"))
      (node (ref "R9") (pin "1") (pinfunction "1_1") (pintype "passive"))
      (node (ref "U2") (pin "27") (pinfunction "IDRIVE_27") (pintype "passive"))
    )
    (net (code "54") (name "Net-(U2-MODE)") (class "Default")
      (node (ref "R6") (pin "2") (pinfunction "2_2") (pintype "passive"))
      (node (ref "R7") (pin "1") (pinfunction "1_1") (pintype "passive"))
      (node (ref "U2") (pin "26") (pinfunction "MODE_26") (pintype "passive"))
    )
    (net (code "55") (name "Net-(U2-VCP)") (class "Default")
      (node (ref "C9") (pin "1") (pinfunction "1_1") (pintype "passive"))
      (node (ref "U2") (pin "3") (pinfunction "VCP_3") (pintype "passive"))
    )
    (net (code "56") (name "Net-(U2-VDS)") (class "Default")
      (node (ref "R11") (pin "2") (pinfunction "2_2") (pintype "passive"))
      (node (ref "R12") (pin "1") (pinfunction "1_1") (pintype "passive"))
      (node (ref "U2") (pin "28") (pinfunction "VDS_28") (pintype "passive"))
    )
    (net (code "57") (name "Net-(U5-BST)") (class "Default")
      (node (ref "C20") (pin "1") (pinfunction "1_1") (pintype "passive"))
      (node (ref "U5") (pin "4") (pinfunction "BST_4") (pintype "passive"))
    )
    (net (code "58") (name "Net-(U5-EN{slash}SYNC)") (class "Default")
      (node (ref "R25") (pin "2") (pinfunction "2_2") (pintype "passive"))
      (node (ref "U5") (pin "3") (pinfunction "EN/SYNC_3") (pintype "passive"))
    )
    (net (code "59") (name "Net-(U5-FB)") (class "Default")
      (node (ref "R27") (pin "1") (pinfunction "1_1") (pintype "passive"))
      (node (ref "U5") (pin "1") (pinfunction "FB_1") (pintype "passive"))
    )
    (net (code "60") (name "Net-(U5-SW)") (class "Default")
      (node (ref "C20") (pin "2") (pinfunction "2_2") (pintype "passive"))
      (node (ref "L2") (pin "1") (pinfunction "1_1") (pintype "passive"))
      (node (ref "U5") (pin "6") (pinfunction "SW_6") (pintype "passive"))
    )
    (net (code "61") (name "Net-(U5-VCC)") (class "Default")
      (node (ref "C27") (pin "2") (pinfunction "2_2") (pintype "passive"))
      (node (ref "U5") (pin "2") (pinfunction "VCC_2") (pintype "passive"))
    )
    (net (code "62") (name "PGND") (class "Default")
      (node (ref "C1") (pin "1") (pinfunction "1_1") (pintype "passive"))
      (node (ref "C13") (pin "1") (pinfunction "1_1") (pintype "passive"))
      (node (ref "C16") (pin "1") (pinfunction "1_1") (pintype "passive"))
      (node (ref "C17") (pin "1") (pinfunction "1_1") (pintype "passive"))
      (node (ref "C2") (pin "1") (pinfunction "1_1") (pintype "passive"))
      (node (ref "C21") (pin "1") (pinfunction "1_1") (pintype "passive"))
      (node (ref "C22") (pin "1") (pinfunction "1_1") (pintype "passive"))
      (node (ref "C24") (pin "1") (pinfunction "1_1") (pintype "passive"))
      (node (ref "C25") (pin "1") (pinfunction "1_1") (pintype "passive"))
      (node (ref "C27") (pin "1") (pinfunction "1_1") (pintype "passive"))
      (node (ref "C3") (pin "1") (pinfunction "1_1") (pintype "passive"))
      (node (ref "C4") (pin "1") (pinfunction "1_1") (pintype "passive"))
      (node (ref "C5") (pin "1") (pinfunction "1_1") (pintype "passive"))
      (node (ref "C6") (pin "1") (pinfunction "1_1") (pintype "passive"))
      (node (ref "C7") (pin "1") (pinfunction "1_1") (pintype "passive"))
      (node (ref "C8") (pin "1") (pinfunction "1_1") (pintype "passive"))
      (node (ref "CN4") (pin "2") (pinfunction "-_2") (pintype "passive"))
      (node (ref "D7") (pin "2") (pinfunction "A_2") (pintype "passive"))
      (node (ref "R13") (pin "1") (pinfunction "1_1") (pintype "passive"))
      (node (ref "R17") (pin "1") (pinfunction "1_1") (pintype "passive"))
      (node (ref "R18") (pin "1") (pinfunction "1_1") (pintype "passive"))
      (node (ref "R23") (pin "2") (pinfunction "2_2") (pintype "passive"))
      (node (ref "R24") (pin "2") (pinfunction "2_2") (pintype "passive"))
      (node (ref "R28") (pin "1") (pinfunction "1_1") (pintype "passive"))
      (node (ref "R5") (pin "2") (pinfunction "2_2") (pintype "passive"))
      (node (ref "U2") (pin "10") (pinfunction "SNA_10") (pintype "passive"))
      (node (ref "U2") (pin "11") (pinfunction "SNB_11") (pintype "passive"))
      (node (ref "U2") (pin "20") (pinfunction "SNC_20") (pintype "passive"))
      (node (ref "U2") (pin "40") (pinfunction "PGND_40") (pintype "passive"))
      (node (ref "U2") (pin "41") (pinfunction "EP_41") (pintype "passive"))
      (node (ref "U3") (pin "2") (pinfunction "GND_2") (pintype "passive"))
      (node (ref "U5") (pin "5") (pinfunction "GND_5") (pintype "passive"))
    )
    (net (code "63") (name "VBUS") (class "Default")
      (node (ref "C1") (pin "2") (pinfunction "2_2") (pintype "passive"))
      (node (ref "C13") (pin "2") (pinfunction "2_2") (pintype "passive"))
      (node (ref "C2") (pin "2") (pinfunction "2_2") (pintype "passive"))
      (node (ref "C21") (pin "2") (pinfunction "2_2") (pintype "passive"))
      (node (ref "C22") (pin "2") (pinfunction "2_2") (pintype "passive"))
      (node (ref "C3") (pin "2") (pinfunction "2_2") (pintype "passive"))
      (node (ref "C4") (pin "2") (pinfunction "2_2") (pintype "passive"))
      (node (ref "C5") (pin "2") (pinfunction "2_2") (pintype "passive"))
      (node (ref "C6") (pin "2") (pinfunction "2_2") (pintype "passive"))
      (node (ref "C7") (pin "2") (pinfunction "2_2") (pintype "passive"))
      (node (ref "C8") (pin "2") (pinfunction "2_2") (pintype "passive"))
      (node (ref "C9") (pin "2") (pinfunction "2_2") (pintype "passive"))
      (node (ref "CN4") (pin "1") (pinfunction "+_1") (pintype "passive"))
      (node (ref "D1") (pin "2") (pinfunction "D_2") (pintype "passive"))
      (node (ref "D3") (pin "2") (pinfunction "D_2") (pintype "passive"))
      (node (ref "D5") (pin "2") (pinfunction "D_2") (pintype "passive"))
      (node (ref "D7") (pin "1") (pinfunction "K_1") (pintype "passive"))
      (node (ref "R21") (pin "2") (pinfunction "2_2") (pintype "passive"))
      (node (ref "R25") (pin "1") (pinfunction "1_1") (pintype "passive"))
      (node (ref "U2") (pin "4") (pinfunction "VM_4") (pintype "passive"))
      (node (ref "U2") (pin "5") (pinfunction "VDRAIN_5") (pintype "passive"))
      (node (ref "U5") (pin "7") (pinfunction "IN_7") (pintype "passive"))
    )
    (net (code "64") (name "unconnected-(U3-NC-Pad4)") (class "Default")
      (node (ref "U3") (pin "4") (pinfunction "NC_4") (pintype "passive+no_connect"))
    )
    (net (code "65") (name "unconnected-(U5-PG-Pad8)") (class "Default")
      (node (ref "U5") (pin "8") (pinfunction "PG_8") (pintype "passive+no_connect"))
    )
  )
)
